# dac-digital.net
KiCad netlist of a schematic drawn in Altium Designer
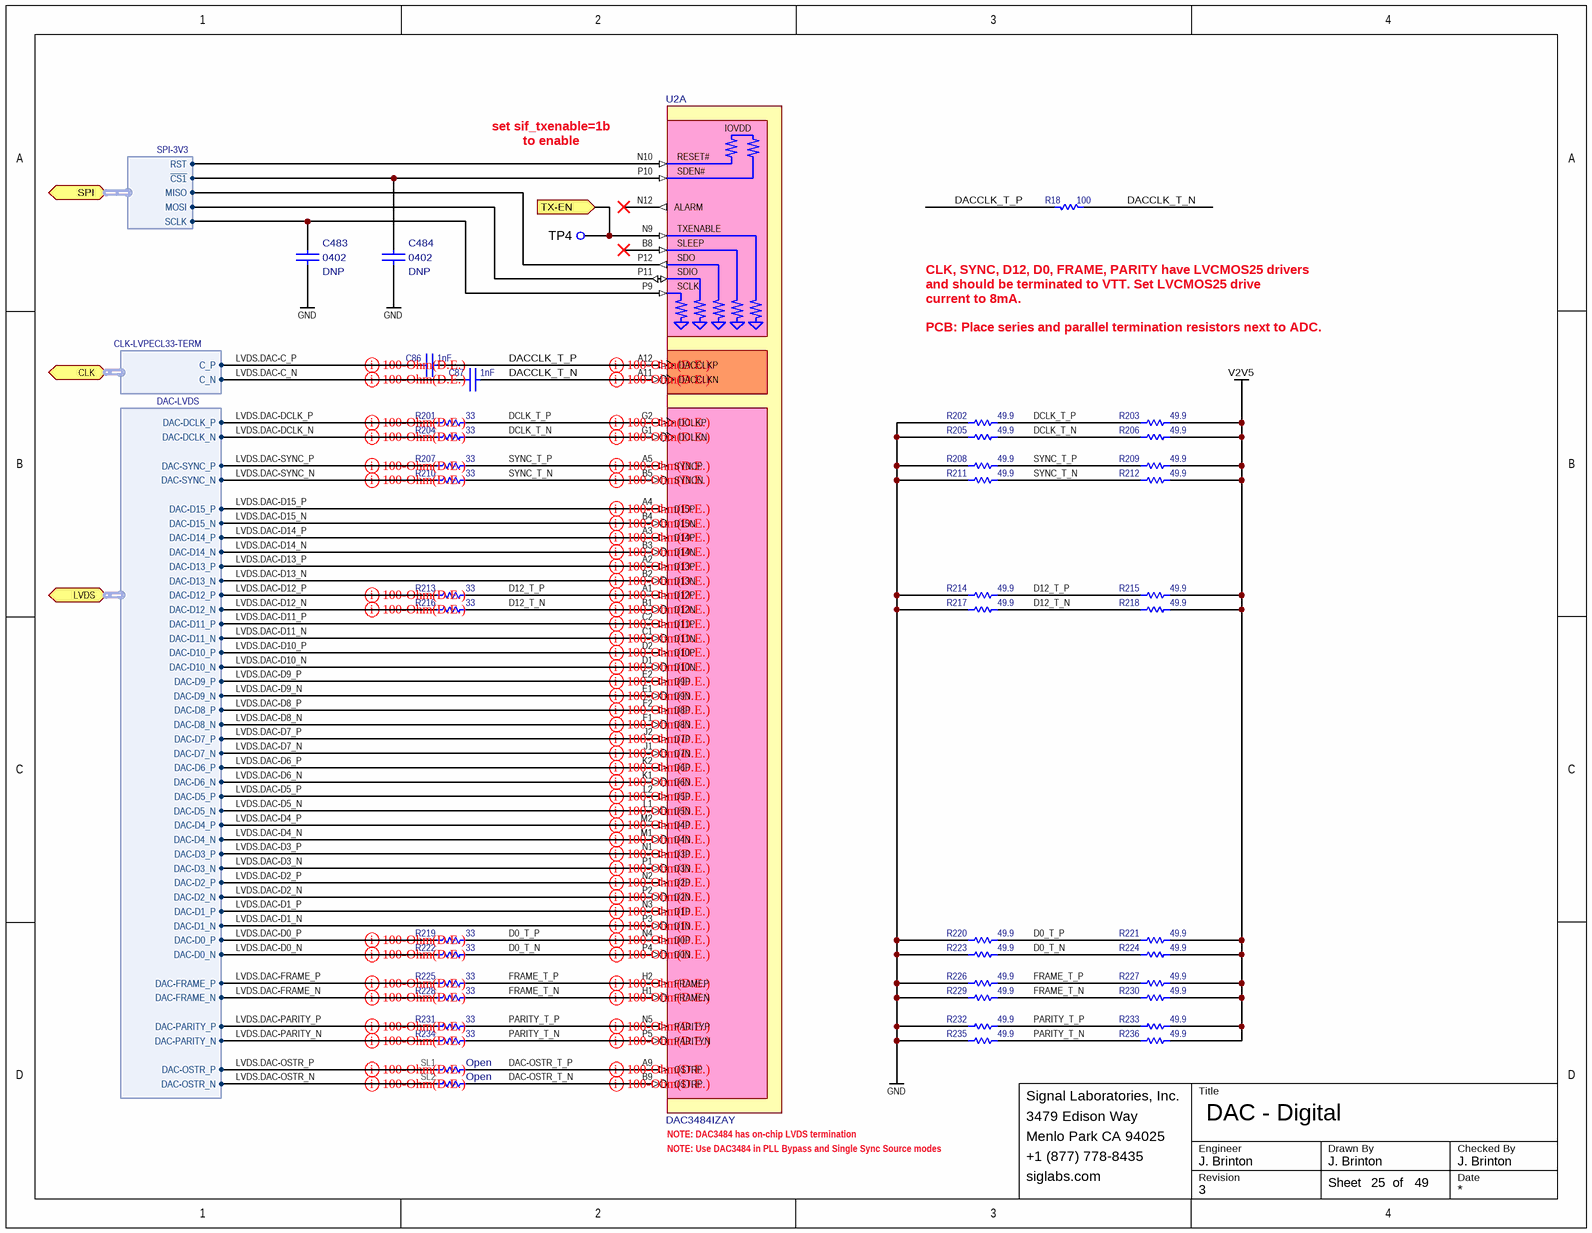
[diagram p0: dac-digital.SchDoc]

(export (version "E")
  (design (tool "Eeschema 10.0.6"))
  (components
    (comp (ref "C86")
      (value "1nF")
      (footprint "CAPC100X50X55L25N")
      (description "Ceramic Capacitor 1nF ±5% 50V NP0 0402")
      (fields (field (name "VOLTAGE") "50V") (field (name "MANUFACTURER") "TDK"))
      (libsource (lib "Graviton") (part "CAP 0402"))
    )
    (comp (ref "C87")
      (value "1nF")
      (footprint "CAPC100X50X55L25N")
      (description "Ceramic Capacitor 1nF ±5% 50V NP0 0402")
      (fields (field (name "VOLTAGE") "50V") (field (name "MANUFACTURER") "TDK"))
      (libsource (lib "Graviton") (part "CAP 0402"))
    )
    (comp (ref "C483")
      (value "VJ0402A101KXA")
      (footprint "CAPC100X50X55L25N")
      (description "Ceramic Capacitor 100pF ±10% 50V C0G 0402")
      (fields
        (field (name "MANUFACTURER") "Vishay")
        (field (name "TOLERANCE") "±10%")
        (field (name "PACKAGE") "0402")
        (field (name "DO NOT PLACE") "DNP")
      )
      (libsource (lib "capacitors") (part "CAP"))
    )
    (comp (ref "C484")
      (value "VJ0402A101KXA")
      (footprint "CAPC100X50X55L25N")
      (description "Ceramic Capacitor 100pF ±10% 50V C0G 0402")
      (fields
        (field (name "MANUFACTURER") "Vishay")
        (field (name "TOLERANCE") "±10%")
        (field (name "PACKAGE") "0402")
        (field (name "DO NOT PLACE") "DNP")
      )
      (libsource (lib "capacitors") (part "CAP"))
    )
    (comp (ref "R18")
      (value "100")
      (footprint "RESC1005X40N")
      (description "Thin Film Resistor 100 ±0.1% 0402")
      (fields (field (name "MANUFACTURER") "Panasonic") (field (name "TOLERANCE") "±0.1%"))
      (libsource (lib "Graviton") (part "RES 0402"))
    )
    (comp (ref "R201")
      (value "33")
      (footprint "generic:RESC1005X40N")
      (description "Thin Film Resistor 33 Ohm ±1% 0402")
      (fields (field (name "MANUFACTURER") "Vishay") (field (name "TOLERANCE") "±1%"))
      (libsource (lib "Graviton") (part "RES 0603"))
    )
    (comp (ref "R202")
      (value "49.9")
      (footprint "generic:RESC1005X40N")
      (description "Thin Film Resistor 49.9 Ohm ±1% 0402")
      (fields (field (name "MANUFACTURER") "Vishay") (field (name "TOLERANCE") "±1%"))
      (libsource (lib "Graviton") (part "RES 0603"))
    )
    (comp (ref "R203")
      (value "49.9")
      (footprint "generic:RESC1005X40N")
      (description "Thin Film Resistor 49.9 Ohm ±1% 0402")
      (fields (field (name "MANUFACTURER") "Vishay") (field (name "TOLERANCE") "±1%"))
      (libsource (lib "Graviton") (part "RES 0603"))
    )
    (comp (ref "R204")
      (value "33")
      (footprint "generic:RESC1005X40N")
      (description "Thin Film Resistor 33 Ohm ±1% 0402")
      (fields (field (name "MANUFACTURER") "Vishay") (field (name "TOLERANCE") "±1%"))
      (libsource (lib "Graviton") (part "RES 0603"))
    )
    (comp (ref "R205")
      (value "49.9")
      (footprint "generic:RESC1005X40N")
      (description "Thin Film Resistor 49.9 Ohm ±1% 0402")
      (fields (field (name "MANUFACTURER") "Vishay") (field (name "TOLERANCE") "±1%"))
      (libsource (lib "Graviton") (part "RES 0603"))
    )
    (comp (ref "R206")
      (value "49.9")
      (footprint "generic:RESC1005X40N")
      (description "Thin Film Resistor 49.9 Ohm ±1% 0402")
      (fields (field (name "MANUFACTURER") "Vishay") (field (name "TOLERANCE") "±1%"))
      (libsource (lib "Graviton") (part "RES 0603"))
    )
    (comp (ref "R207")
      (value "33")
      (footprint "generic:RESC1005X40N")
      (description "Thin Film Resistor 33 Ohm ±1% 0402")
      (fields (field (name "MANUFACTURER") "Vishay") (field (name "TOLERANCE") "±1%"))
      (libsource (lib "Graviton") (part "RES 0603"))
    )
    (comp (ref "R208")
      (value "49.9")
      (footprint "generic:RESC1005X40N")
      (description "Thin Film Resistor 49.9 Ohm ±1% 0402")
      (fields (field (name "MANUFACTURER") "Vishay") (field (name "TOLERANCE") "±1%"))
      (libsource (lib "Graviton") (part "RES 0603"))
    )
    (comp (ref "R209")
      (value "49.9")
      (footprint "generic:RESC1005X40N")
      (description "Thin Film Resistor 49.9 Ohm ±1% 0402")
      (fields (field (name "MANUFACTURER") "Vishay") (field (name "TOLERANCE") "±1%"))
      (libsource (lib "Graviton") (part "RES 0603"))
    )
    (comp (ref "R210")
      (value "33")
      (footprint "generic:RESC1005X40N")
      (description "Thin Film Resistor 33 Ohm ±1% 0402")
      (fields (field (name "MANUFACTURER") "Vishay") (field (name "TOLERANCE") "±1%"))
      (libsource (lib "Graviton") (part "RES 0603"))
    )
    (comp (ref "R211")
      (value "49.9")
      (footprint "generic:RESC1005X40N")
      (description "Thin Film Resistor 49.9 Ohm ±1% 0402")
      (fields (field (name "MANUFACTURER") "Vishay") (field (name "TOLERANCE") "±1%"))
      (libsource (lib "Graviton") (part "RES 0603"))
    )
    (comp (ref "R212")
      (value "49.9")
      (footprint "generic:RESC1005X40N")
      (description "Thin Film Resistor 49.9 Ohm ±1% 0402")
      (fields (field (name "MANUFACTURER") "Vishay") (field (name "TOLERANCE") "±1%"))
      (libsource (lib "Graviton") (part "RES 0603"))
    )
    (comp (ref "R213")
      (value "33")
      (footprint "generic:RESC1005X40N")
      (description "Thin Film Resistor 33 Ohm ±1% 0402")
      (fields (field (name "MANUFACTURER") "Vishay") (field (name "TOLERANCE") "±1%"))
      (libsource (lib "Graviton") (part "RES 0603"))
    )
    (comp (ref "R214")
      (value "49.9")
      (footprint "generic:RESC1005X40N")
      (description "Thin Film Resistor 49.9 Ohm ±1% 0402")
      (fields (field (name "MANUFACTURER") "Vishay") (field (name "TOLERANCE") "±1%"))
      (libsource (lib "Graviton") (part "RES 0603"))
    )
    (comp (ref "R215")
      (value "49.9")
      (footprint "generic:RESC1005X40N")
      (description "Thin Film Resistor 49.9 Ohm ±1% 0402")
      (fields (field (name "MANUFACTURER") "Vishay") (field (name "TOLERANCE") "±1%"))
      (libsource (lib "Graviton") (part "RES 0603"))
    )
    (comp (ref "R216")
      (value "33")
      (footprint "generic:RESC1005X40N")
      (description "Thin Film Resistor 33 Ohm ±1% 0402")
      (fields (field (name "MANUFACTURER") "Vishay") (field (name "TOLERANCE") "±1%"))
      (libsource (lib "Graviton") (part "RES 0603"))
    )
    (comp (ref "R217")
      (value "49.9")
      (footprint "generic:RESC1005X40N")
      (description "Thin Film Resistor 49.9 Ohm ±1% 0402")
      (fields (field (name "MANUFACTURER") "Vishay") (field (name "TOLERANCE") "±1%"))
      (libsource (lib "Graviton") (part "RES 0603"))
    )
    (comp (ref "R218")
      (value "49.9")
      (footprint "generic:RESC1005X40N")
      (description "Thin Film Resistor 49.9 Ohm ±1% 0402")
      (fields (field (name "MANUFACTURER") "Vishay") (field (name "TOLERANCE") "±1%"))
      (libsource (lib "Graviton") (part "RES 0603"))
    )
    (comp (ref "R219")
      (value "33")
      (footprint "generic:RESC1005X40N")
      (description "Thin Film Resistor 33 Ohm ±1% 0402")
      (fields (field (name "MANUFACTURER") "Vishay") (field (name "TOLERANCE") "±1%"))
      (libsource (lib "Graviton") (part "RES 0603"))
    )
    (comp (ref "R220")
      (value "49.9")
      (footprint "generic:RESC1005X40N")
      (description "Thin Film Resistor 49.9 Ohm ±1% 0402")
      (fields (field (name "MANUFACTURER") "Vishay") (field (name "TOLERANCE") "±1%"))
      (libsource (lib "Graviton") (part "RES 0603"))
    )
    (comp (ref "R221")
      (value "49.9")
      (footprint "generic:RESC1005X40N")
      (description "Thin Film Resistor 49.9 Ohm ±1% 0402")
      (fields (field (name "MANUFACTURER") "Vishay") (field (name "TOLERANCE") "±1%"))
      (libsource (lib "Graviton") (part "RES 0603"))
    )
    (comp (ref "R222")
      (value "33")
      (footprint "generic:RESC1005X40N")
      (description "Thin Film Resistor 33 Ohm ±1% 0402")
      (fields (field (name "MANUFACTURER") "Vishay") (field (name "TOLERANCE") "±1%"))
      (libsource (lib "Graviton") (part "RES 0603"))
    )
    (comp (ref "R223")
      (value "49.9")
      (footprint "generic:RESC1005X40N")
      (description "Thin Film Resistor 49.9 Ohm ±1% 0402")
      (fields (field (name "MANUFACTURER") "Vishay") (field (name "TOLERANCE") "±1%"))
      (libsource (lib "Graviton") (part "RES 0603"))
    )
    (comp (ref "R224")
      (value "49.9")
      (footprint "generic:RESC1005X40N")
      (description "Thin Film Resistor 49.9 Ohm ±1% 0402")
      (fields (field (name "MANUFACTURER") "Vishay") (field (name "TOLERANCE") "±1%"))
      (libsource (lib "Graviton") (part "RES 0603"))
    )
    (comp (ref "R225")
      (value "33")
      (footprint "generic:RESC1005X40N")
      (description "Thin Film Resistor 33 Ohm ±1% 0402")
      (fields (field (name "MANUFACTURER") "Vishay") (field (name "TOLERANCE") "±1%"))
      (libsource (lib "Graviton") (part "RES 0603"))
    )
    (comp (ref "R226")
      (value "49.9")
      (footprint "generic:RESC1005X40N")
      (description "Thin Film Resistor 49.9 Ohm ±1% 0402")
      (fields (field (name "MANUFACTURER") "Vishay") (field (name "TOLERANCE") "±1%"))
      (libsource (lib "Graviton") (part "RES 0603"))
    )
    (comp (ref "R227")
      (value "49.9")
      (footprint "generic:RESC1005X40N")
      (description "Thin Film Resistor 49.9 Ohm ±1% 0402")
      (fields (field (name "MANUFACTURER") "Vishay") (field (name "TOLERANCE") "±1%"))
      (libsource (lib "Graviton") (part "RES 0603"))
    )
    (comp (ref "R228")
      (value "33")
      (footprint "generic:RESC1005X40N")
      (description "Thin Film Resistor 33 Ohm ±1% 0402")
      (fields (field (name "MANUFACTURER") "Vishay") (field (name "TOLERANCE") "±1%"))
      (libsource (lib "Graviton") (part "RES 0603"))
    )
    (comp (ref "R229")
      (value "49.9")
      (footprint "generic:RESC1005X40N")
      (description "Thin Film Resistor 49.9 Ohm ±1% 0402")
      (fields (field (name "MANUFACTURER") "Vishay") (field (name "TOLERANCE") "±1%"))
      (libsource (lib "Graviton") (part "RES 0603"))
    )
    (comp (ref "R230")
      (value "49.9")
      (footprint "generic:RESC1005X40N")
      (description "Thin Film Resistor 49.9 Ohm ±1% 0402")
      (fields (field (name "MANUFACTURER") "Vishay") (field (name "TOLERANCE") "±1%"))
      (libsource (lib "Graviton") (part "RES 0603"))
    )
    (comp (ref "R231")
      (value "33")
      (footprint "generic:RESC1005X40N")
      (description "Thin Film Resistor 33 Ohm ±1% 0402")
      (fields (field (name "MANUFACTURER") "Vishay") (field (name "TOLERANCE") "±1%"))
      (libsource (lib "Graviton") (part "RES 0603"))
    )
    (comp (ref "R232")
      (value "49.9")
      (footprint "generic:RESC1005X40N")
      (description "Thin Film Resistor 49.9 Ohm ±1% 0402")
      (fields (field (name "MANUFACTURER") "Vishay") (field (name "TOLERANCE") "±1%"))
      (libsource (lib "Graviton") (part "RES 0603"))
    )
    (comp (ref "R233")
      (value "49.9")
      (footprint "generic:RESC1005X40N")
      (description "Thin Film Resistor 49.9 Ohm ±1% 0402")
      (fields (field (name "MANUFACTURER") "Vishay") (field (name "TOLERANCE") "±1%"))
      (libsource (lib "Graviton") (part "RES 0603"))
    )
    (comp (ref "R234")
      (value "33")
      (footprint "generic:RESC1005X40N")
      (description "Thin Film Resistor 33 Ohm ±1% 0402")
      (fields (field (name "MANUFACTURER") "Vishay") (field (name "TOLERANCE") "±1%"))
      (libsource (lib "Graviton") (part "RES 0603"))
    )
    (comp (ref "R235")
      (value "49.9")
      (footprint "generic:RESC1005X40N")
      (description "Thin Film Resistor 49.9 Ohm ±1% 0402")
      (fields (field (name "MANUFACTURER") "Vishay") (field (name "TOLERANCE") "±1%"))
      (libsource (lib "Graviton") (part "RES 0603"))
    )
    (comp (ref "R236")
      (value "49.9")
      (footprint "generic:RESC1005X40N")
      (description "Thin Film Resistor 49.9 Ohm ±1% 0402")
      (fields (field (name "MANUFACTURER") "Vishay") (field (name "TOLERANCE") "±1%"))
      (libsource (lib "Graviton") (part "RES 0603"))
    )
    (comp (ref "SL1")
      (value "SOLDER_LINK")
      (footprint "SOLDERLINK0603X26N")
      (description "Solder Link, Open")
      (fields (field (name "NOTES") "Open"))
      (libsource (lib "generic") (part "RES"))
    )
    (comp (ref "SL2")
      (value "SOLDER_LINK")
      (footprint "SOLDERLINK0603X26N")
      (description "Solder Link, Open")
      (fields (field (name "NOTES") "Open"))
      (libsource (lib "generic") (part "RES"))
    )
    (comp (ref "TP4")
      (value "TEST_POINT_SMD_10")
      (footprint "generic:TEST_POINT_SMD_10")
      (description "Test Point SMD")
      (libsource (lib "generic") (part "TEST_POINT_SMD_10"))
    )
    (comp (ref "U2")
      (value "DAC3484IZAY")
      (footprint "ZAY-BGA-196")
      (description "High Speed Quad DAC, 16-bit, 1.25GSPS")
      (fields (field (name "MANUFACTURER") "Texas Instruments"))
      (libsource (lib "ti") (part "DAC3484IZAY"))
    )
  )
  (nets
    (net (code "4") (name "/D0_T_N") (class "Default")
      (node (ref "R222") (pin "1") (pinfunction "1_1") (pintype "passive"))
      (node (ref "R223") (pin "1") (pinfunction "1_1") (pintype "passive"))
      (node (ref "R224") (pin "2") (pinfunction "2_2") (pintype "passive"))
      (node (ref "U2") (pin "P4") (pinfunction "D0N_P4") (pintype "input"))
    )
    (net (code "5") (name "/D0_T_P") (class "Default")
      (node (ref "R219") (pin "1") (pinfunction "1_1") (pintype "passive"))
      (node (ref "R220") (pin "1") (pinfunction "1_1") (pintype "passive"))
      (node (ref "R221") (pin "2") (pinfunction "2_2") (pintype "passive"))
      (node (ref "U2") (pin "N4") (pinfunction "D0P_N4") (pintype "input"))
    )
    (net (code "6") (name "/D12_T_N") (class "Default")
      (node (ref "R216") (pin "1") (pinfunction "1_1") (pintype "passive"))
      (node (ref "R217") (pin "1") (pinfunction "1_1") (pintype "passive"))
      (node (ref "R218") (pin "2") (pinfunction "2_2") (pintype "passive"))
      (node (ref "U2") (pin "B1") (pinfunction "D12N_B1") (pintype "input"))
    )
    (net (code "7") (name "/D12_T_P") (class "Default")
      (node (ref "R213") (pin "1") (pinfunction "1_1") (pintype "passive"))
      (node (ref "R214") (pin "1") (pinfunction "1_1") (pintype "passive"))
      (node (ref "R215") (pin "2") (pinfunction "2_2") (pintype "passive"))
      (node (ref "U2") (pin "A1") (pinfunction "D12P_A1") (pintype "input"))
    )
    (net (code "8") (name "/DAC-OSTR_T_N") (class "Default")
      (node (ref "SL2") (pin "1") (pinfunction "1_1") (pintype "passive"))
      (node (ref "U2") (pin "B9") (pinfunction "OSTRP_B9") (pintype "input"))
    )
    (net (code "9") (name "/DAC-OSTR_T_P") (class "Default")
      (node (ref "SL1") (pin "1") (pinfunction "1_1") (pintype "passive"))
      (node (ref "U2") (pin "A9") (pinfunction "OSTRP_A9") (pintype "input"))
    )
    (net (code "10") (name "/DACCLK_T_N") (class "Default")
      (node (ref "C87") (pin "1") (pinfunction "1_1") (pintype "passive"))
      (node (ref "R18") (pin "2") (pinfunction "2_2") (pintype "passive"))
      (node (ref "U2") (pin "A11") (pinfunction "DACCLKN_A11") (pintype "input"))
    )
    (net (code "11") (name "/DACCLK_T_P") (class "Default")
      (node (ref "C86") (pin "1") (pinfunction "1_1") (pintype "passive"))
      (node (ref "R18") (pin "1") (pinfunction "1_1") (pintype "passive"))
      (node (ref "U2") (pin "A12") (pinfunction "DACCLKP_A12") (pintype "input"))
    )
    (net (code "12") (name "/DCLK_T_N") (class "Default")
      (node (ref "R204") (pin "1") (pinfunction "1_1") (pintype "passive"))
      (node (ref "R205") (pin "1") (pinfunction "1_1") (pintype "passive"))
      (node (ref "R206") (pin "2") (pinfunction "2_2") (pintype "passive"))
      (node (ref "U2") (pin "G1") (pinfunction "DCLKN_G1") (pintype "input"))
    )
    (net (code "13") (name "/DCLK_T_P") (class "Default")
      (node (ref "R201") (pin "1") (pinfunction "1_1") (pintype "passive"))
      (node (ref "R202") (pin "1") (pinfunction "1_1") (pintype "passive"))
      (node (ref "R203") (pin "2") (pinfunction "2_2") (pintype "passive"))
      (node (ref "U2") (pin "G2") (pinfunction "DCLKP_G2") (pintype "input"))
    )
    (net (code "14") (name "/FRAME_T_N") (class "Default")
      (node (ref "R228") (pin "1") (pinfunction "1_1") (pintype "passive"))
      (node (ref "R229") (pin "1") (pinfunction "1_1") (pintype "passive"))
      (node (ref "R230") (pin "2") (pinfunction "2_2") (pintype "passive"))
      (node (ref "U2") (pin "H1") (pinfunction "FRAMEN_H1") (pintype "input"))
    )
    (net (code "15") (name "/FRAME_T_P") (class "Default")
      (node (ref "R225") (pin "1") (pinfunction "1_1") (pintype "passive"))
      (node (ref "R226") (pin "1") (pinfunction "1_1") (pintype "passive"))
      (node (ref "R227") (pin "2") (pinfunction "2_2") (pintype "passive"))
      (node (ref "U2") (pin "H2") (pinfunction "FRAMEP_H2") (pintype "input"))
    )
    (net (code "16") (name "/LVDS.DAC-C_N") (class "Default")
      (node (ref "C87") (pin "2") (pinfunction "2_2") (pintype "passive"))
    )
    (net (code "17") (name "/LVDS.DAC-C_P") (class "Default")
      (node (ref "C86") (pin "2") (pinfunction "2_2") (pintype "passive"))
    )
    (net (code "18") (name "/LVDS.DAC-D0_N") (class "Default")
      (node (ref "R222") (pin "2") (pinfunction "2_2") (pintype "passive"))
    )
    (net (code "19") (name "/LVDS.DAC-D0_P") (class "Default")
      (node (ref "R219") (pin "2") (pinfunction "2_2") (pintype "passive"))
    )
    (net (code "20") (name "/LVDS.DAC-D1_N") (class "Default")
      (node (ref "U2") (pin "P3") (pinfunction "D1N_P3") (pintype "input"))
    )
    (net (code "21") (name "/LVDS.DAC-D1_P") (class "Default")
      (node (ref "U2") (pin "N3") (pinfunction "D1P_N3") (pintype "input"))
    )
    (net (code "22") (name "/LVDS.DAC-D2_N") (class "Default")
      (node (ref "U2") (pin "P2") (pinfunction "D2N_P2") (pintype "input"))
    )
    (net (code "23") (name "/LVDS.DAC-D2_P") (class "Default")
      (node (ref "U2") (pin "N2") (pinfunction "D2P_N2") (pintype "input"))
    )
    (net (code "24") (name "/LVDS.DAC-D3_N") (class "Default")
      (node (ref "U2") (pin "P1") (pinfunction "D3N_P1") (pintype "input"))
    )
    (net (code "25") (name "/LVDS.DAC-D3_P") (class "Default")
      (node (ref "U2") (pin "N1") (pinfunction "D3P_N1") (pintype "input"))
    )
    (net (code "26") (name "/LVDS.DAC-D4_N") (class "Default")
      (node (ref "U2") (pin "M1") (pinfunction "D4N_M1") (pintype "input"))
    )
    (net (code "27") (name "/LVDS.DAC-D4_P") (class "Default")
      (node (ref "U2") (pin "M2") (pinfunction "D4P_M2") (pintype "input"))
    )
    (net (code "28") (name "/LVDS.DAC-D5_N") (class "Default")
      (node (ref "U2") (pin "L1") (pinfunction "D5N_L1") (pintype "input"))
    )
    (net (code "29") (name "/LVDS.DAC-D5_P") (class "Default")
      (node (ref "U2") (pin "L2") (pinfunction "D5P_L2") (pintype "input"))
    )
    (net (code "30") (name "/LVDS.DAC-D6_N") (class "Default")
      (node (ref "U2") (pin "K1") (pinfunction "D6N_K1") (pintype "input"))
    )
    (net (code "31") (name "/LVDS.DAC-D6_P") (class "Default")
      (node (ref "U2") (pin "K2") (pinfunction "D6P_K2") (pintype "input"))
    )
    (net (code "32") (name "/LVDS.DAC-D7_N") (class "Default")
      (node (ref "U2") (pin "J1") (pinfunction "D7N_J1") (pintype "input"))
    )
    (net (code "33") (name "/LVDS.DAC-D7_P") (class "Default")
      (node (ref "U2") (pin "J2") (pinfunction "D7P_J2") (pintype "input"))
    )
    (net (code "34") (name "/LVDS.DAC-D8_N") (class "Default")
      (node (ref "U2") (pin "F1") (pinfunction "D8N_F1") (pintype "input"))
    )
    (net (code "35") (name "/LVDS.DAC-D8_P") (class "Default")
      (node (ref "U2") (pin "F2") (pinfunction "D8P_F2") (pintype "input"))
    )
    (net (code "36") (name "/LVDS.DAC-D9_N") (class "Default")
      (node (ref "U2") (pin "E1") (pinfunction "D9N_E1") (pintype "input"))
    )
    (net (code "37") (name "/LVDS.DAC-D9_P") (class "Default")
      (node (ref "U2") (pin "E2") (pinfunction "D9P_E2") (pintype "input"))
    )
    (net (code "38") (name "/LVDS.DAC-D10_N") (class "Default")
      (node (ref "U2") (pin "D1") (pinfunction "D10N_D1") (pintype "input"))
    )
    (net (code "39") (name "/LVDS.DAC-D10_P") (class "Default")
      (node (ref "U2") (pin "D2") (pinfunction "D10P_D2") (pintype "input"))
    )
    (net (code "40") (name "/LVDS.DAC-D11_N") (class "Default")
      (node (ref "U2") (pin "C1") (pinfunction "D11N_C1") (pintype "input"))
    )
    (net (code "41") (name "/LVDS.DAC-D11_P") (class "Default")
      (node (ref "U2") (pin "C2") (pinfunction "D11P_C2") (pintype "input"))
    )
    (net (code "42") (name "/LVDS.DAC-D12_N") (class "Default")
      (node (ref "R216") (pin "2") (pinfunction "2_2") (pintype "passive"))
    )
    (net (code "43") (name "/LVDS.DAC-D12_P") (class "Default")
      (node (ref "R213") (pin "2") (pinfunction "2_2") (pintype "passive"))
    )
    (net (code "44") (name "/LVDS.DAC-D13_N") (class "Default")
      (node (ref "U2") (pin "B2") (pinfunction "D13N_B2") (pintype "input"))
    )
    (net (code "45") (name "/LVDS.DAC-D13_P") (class "Default")
      (node (ref "U2") (pin "A2") (pinfunction "D13P_A2") (pintype "input"))
    )
    (net (code "46") (name "/LVDS.DAC-D14_N") (class "Default")
      (node (ref "U2") (pin "B3") (pinfunction "D14N_B3") (pintype "input"))
    )
    (net (code "47") (name "/LVDS.DAC-D14_P") (class "Default")
      (node (ref "U2") (pin "A3") (pinfunction "D14P_A3") (pintype "input"))
    )
    (net (code "48") (name "/LVDS.DAC-D15_N") (class "Default")
      (node (ref "U2") (pin "B4") (pinfunction "D15N_B4") (pintype "input"))
    )
    (net (code "49") (name "/LVDS.DAC-D15_P") (class "Default")
      (node (ref "U2") (pin "A4") (pinfunction "D15P_A4") (pintype "input"))
    )
    (net (code "50") (name "/LVDS.DAC-DCLK_N") (class "Default")
      (node (ref "R204") (pin "2") (pinfunction "2_2") (pintype "passive"))
    )
    (net (code "51") (name "/LVDS.DAC-DCLK_P") (class "Default")
      (node (ref "R201") (pin "2") (pinfunction "2_2") (pintype "passive"))
    )
    (net (code "52") (name "/LVDS.DAC-FRAME_N") (class "Default")
      (node (ref "R228") (pin "2") (pinfunction "2_2") (pintype "passive"))
    )
    (net (code "53") (name "/LVDS.DAC-FRAME_P") (class "Default")
      (node (ref "R225") (pin "2") (pinfunction "2_2") (pintype "passive"))
    )
    (net (code "54") (name "/LVDS.DAC-OSTR_N") (class "Default")
      (node (ref "SL2") (pin "2") (pinfunction "2_2") (pintype "passive"))
    )
    (net (code "55") (name "/LVDS.DAC-OSTR_P") (class "Default")
      (node (ref "SL1") (pin "2") (pinfunction "2_2") (pintype "passive"))
    )
    (net (code "56") (name "/LVDS.DAC-PARITY_N") (class "Default")
      (node (ref "R234") (pin "2") (pinfunction "2_2") (pintype "passive"))
    )
    (net (code "57") (name "/LVDS.DAC-PARITY_P") (class "Default")
      (node (ref "R231") (pin "2") (pinfunction "2_2") (pintype "passive"))
    )
    (net (code "58") (name "/LVDS.DAC-SYNC_N") (class "Default")
      (node (ref "R210") (pin "2") (pinfunction "2_2") (pintype "passive"))
    )
    (net (code "59") (name "/LVDS.DAC-SYNC_P") (class "Default")
      (node (ref "R207") (pin "2") (pinfunction "2_2") (pintype "passive"))
    )
    (net (code "60") (name "/MISO") (class "Default")
      (node (ref "U2") (pin "P12") (pinfunction "SDO_P12") (pintype "output"))
    )
    (net (code "61") (name "/MOSI") (class "Default")
      (node (ref "U2") (pin "P11") (pinfunction "SDIO_P11") (pintype "bidirectional"))
    )
    (net (code "62") (name "/PARITY_T_N") (class "Default")
      (node (ref "R234") (pin "1") (pinfunction "1_1") (pintype "passive"))
      (node (ref "R235") (pin "1") (pinfunction "1_1") (pintype "passive"))
      (node (ref "R236") (pin "2") (pinfunction "2_2") (pintype "passive"))
      (node (ref "U2") (pin "P5") (pinfunction "PARITYN_P5") (pintype "input"))
    )
    (net (code "63") (name "/PARITY_T_P") (class "Default")
      (node (ref "R231") (pin "1") (pinfunction "1_1") (pintype "passive"))
      (node (ref "R232") (pin "1") (pinfunction "1_1") (pintype "passive"))
      (node (ref "R233") (pin "2") (pinfunction "2_2") (pintype "passive"))
      (node (ref "U2") (pin "N5") (pinfunction "PARITYP_N5") (pintype "input"))
    )
    (net (code "64") (name "/RST") (class "Default")
      (node (ref "U2") (pin "N10") (pinfunction "RESET_N10") (pintype "input"))
    )
    (net (code "65") (name "/SCLK") (class "Default")
      (node (ref "C483") (pin "1") (pinfunction "1_1") (pintype "passive"))
      (node (ref "U2") (pin "P9") (pinfunction "SCLK_P9") (pintype "input"))
    )
    (net (code "66") (name "/SYNC_T_N") (class "Default")
      (node (ref "R210") (pin "1") (pinfunction "1_1") (pintype "passive"))
      (node (ref "R211") (pin "1") (pinfunction "1_1") (pintype "passive"))
      (node (ref "R212") (pin "2") (pinfunction "2_2") (pintype "passive"))
      (node (ref "U2") (pin "B5") (pinfunction "SYNCN_B5") (pintype "input"))
    )
    (net (code "67") (name "/SYNC_T_P") (class "Default")
      (node (ref "R207") (pin "1") (pinfunction "1_1") (pintype "passive"))
      (node (ref "R208") (pin "1") (pinfunction "1_1") (pintype "passive"))
      (node (ref "R209") (pin "2") (pinfunction "2_2") (pintype "passive"))
      (node (ref "U2") (pin "A5") (pinfunction "SYNCP_A5") (pintype "input"))
    )
    (net (code "68") (name "/TX-EN") (class "Default")
      (node (ref "TP4") (pin "1") (pinfunction "1_1") (pintype "passive"))
      (node (ref "U2") (pin "N9") (pinfunction "TXENABLE_N9") (pintype "input"))
    )
    (net (code "72") (name "/~{CS1}") (class "Default")
      (node (ref "C484") (pin "1") (pinfunction "1_1") (pintype "passive"))
      (node (ref "U2") (pin "P10") (pinfunction "SDEN_P10") (pintype "input"))
    )
    (net (code "73") (name "GND") (class "Default")
      (node (ref "C483") (pin "2") (pinfunction "2_2") (pintype "passive"))
      (node (ref "C484") (pin "2") (pinfunction "2_2") (pintype "passive"))
      (node (ref "R202") (pin "2") (pinfunction "2_2") (pintype "passive"))
      (node (ref "R205") (pin "2") (pinfunction "2_2") (pintype "passive"))
      (node (ref "R208") (pin "2") (pinfunction "2_2") (pintype "passive"))
      (node (ref "R211") (pin "2") (pinfunction "2_2") (pintype "passive"))
      (node (ref "R214") (pin "2") (pinfunction "2_2") (pintype "passive"))
      (node (ref "R217") (pin "2") (pinfunction "2_2") (pintype "passive"))
      (node (ref "R220") (pin "2") (pinfunction "2_2") (pintype "passive"))
      (node (ref "R223") (pin "2") (pinfunction "2_2") (pintype "passive"))
      (node (ref "R226") (pin "2") (pinfunction "2_2") (pintype "passive"))
      (node (ref "R229") (pin "2") (pinfunction "2_2") (pintype "passive"))
      (node (ref "R232") (pin "2") (pinfunction "2_2") (pintype "passive"))
      (node (ref "R235") (pin "2") (pinfunction "2_2") (pintype "passive"))
    )
    (net (code "74") (name "V2V5") (class "Default")
      (node (ref "R203") (pin "1") (pinfunction "1_1") (pintype "passive"))
      (node (ref "R206") (pin "1") (pinfunction "1_1") (pintype "passive"))
      (node (ref "R209") (pin "1") (pinfunction "1_1") (pintype "passive"))
      (node (ref "R212") (pin "1") (pinfunction "1_1") (pintype "passive"))
      (node (ref "R215") (pin "1") (pinfunction "1_1") (pintype "passive"))
      (node (ref "R218") (pin "1") (pinfunction "1_1") (pintype "passive"))
      (node (ref "R221") (pin "1") (pinfunction "1_1") (pintype "passive"))
      (node (ref "R224") (pin "1") (pinfunction "1_1") (pintype "passive"))
      (node (ref "R227") (pin "1") (pinfunction "1_1") (pintype "passive"))
      (node (ref "R230") (pin "1") (pinfunction "1_1") (pintype "passive"))
      (node (ref "R233") (pin "1") (pinfunction "1_1") (pintype "passive"))
      (node (ref "R236") (pin "1") (pinfunction "1_1") (pintype "passive"))
    )
    (net (code "75") (name "unconnected-(U2A-ALARM-PadN12)") (class "Default")
      (node (ref "U2") (pin "N12") (pinfunction "ALARM_N12") (pintype "output+no_connect"))
    )
    (net (code "76") (name "unconnected-(U2A-SLEEP-PadB8)") (class "Default")
      (node (ref "U2") (pin "B8") (pinfunction "SLEEP_B8") (pintype "input+no_connect"))
    )
  )
)
